# Main_PCB.net
KiCad netlist of a schematic drawn in Altium Designer
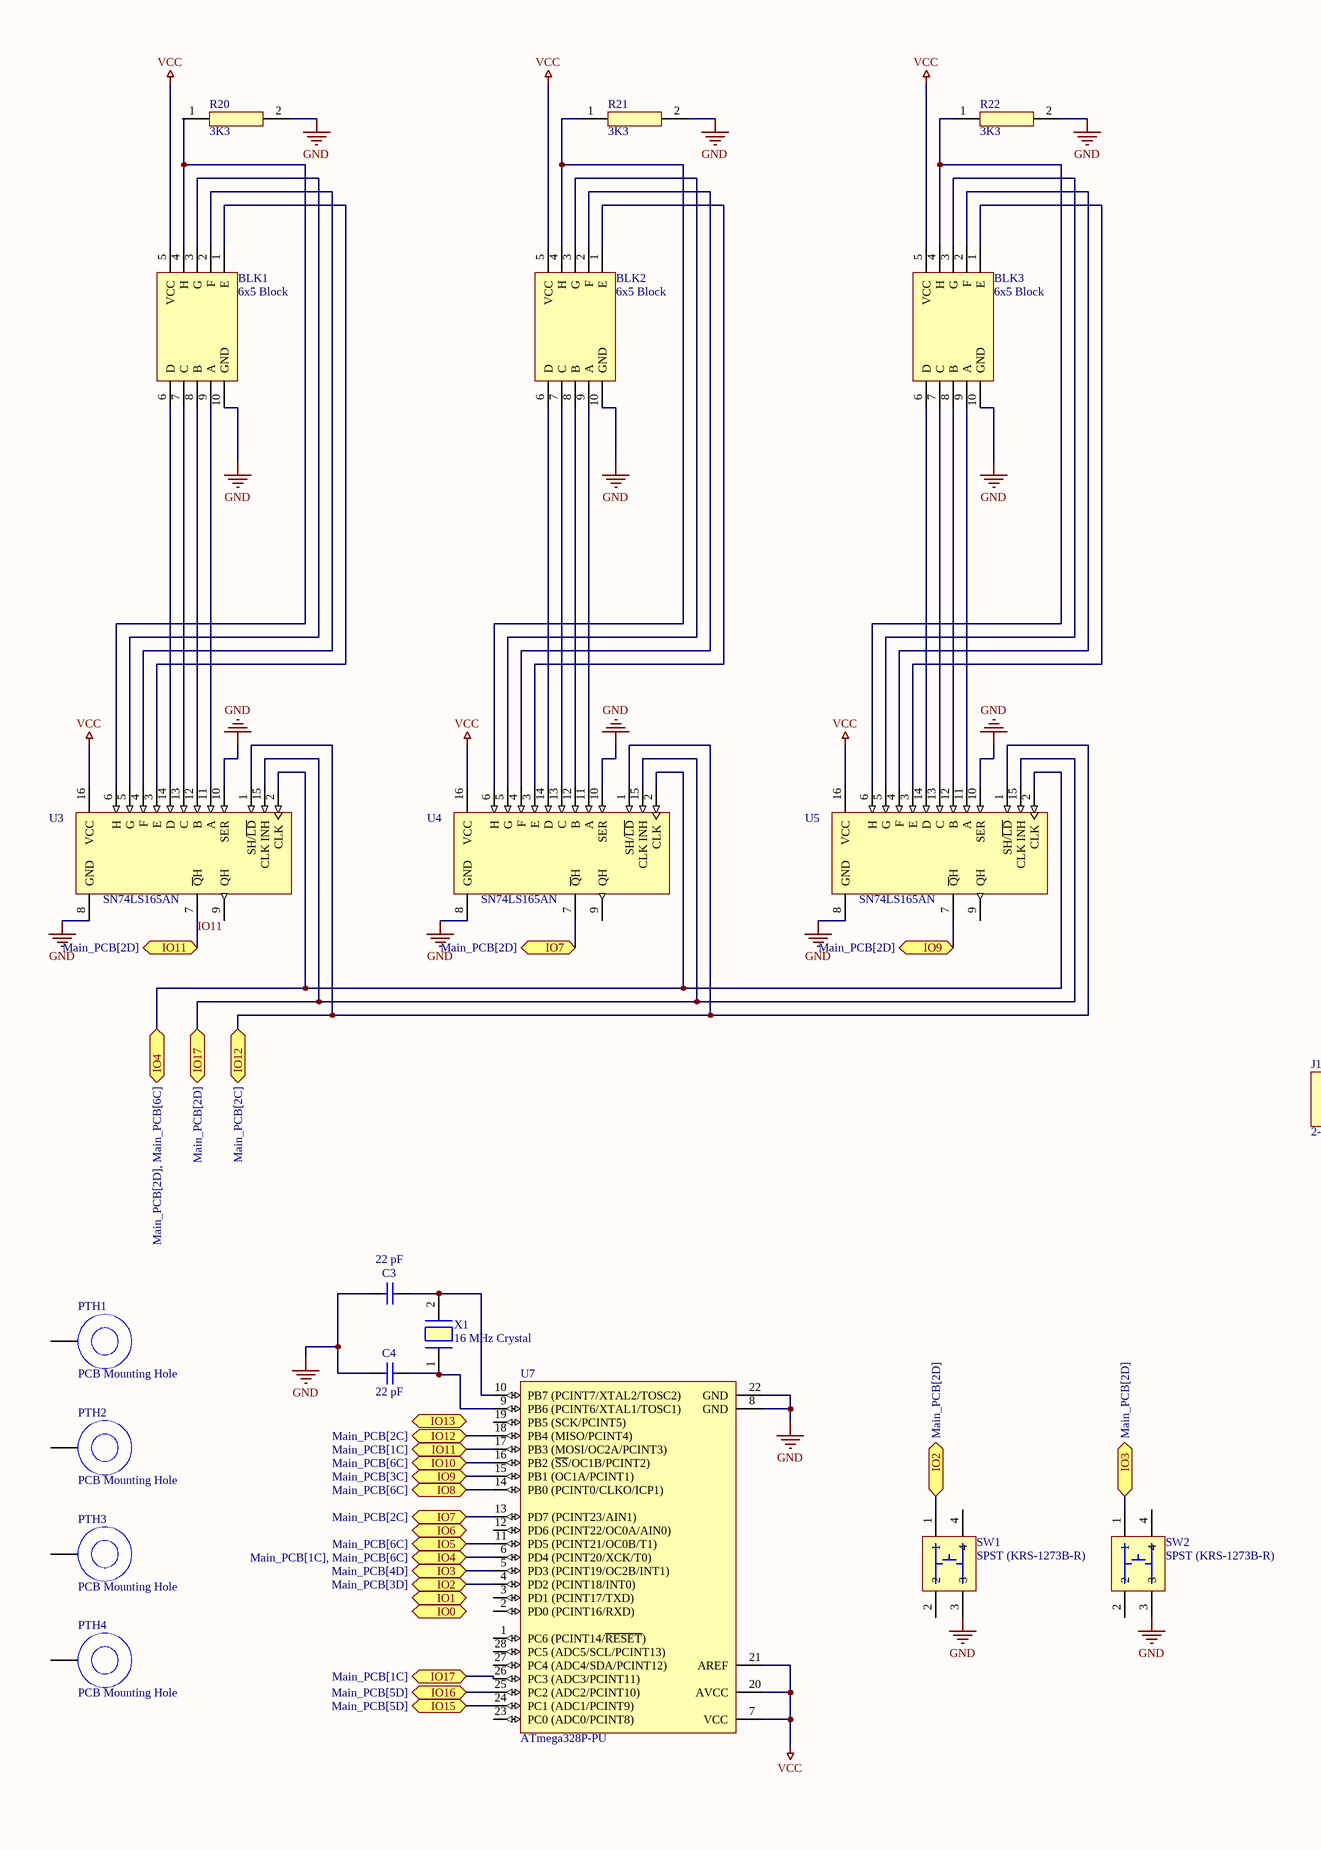
[diagram p0: Main_PCB.SchDoc, left]
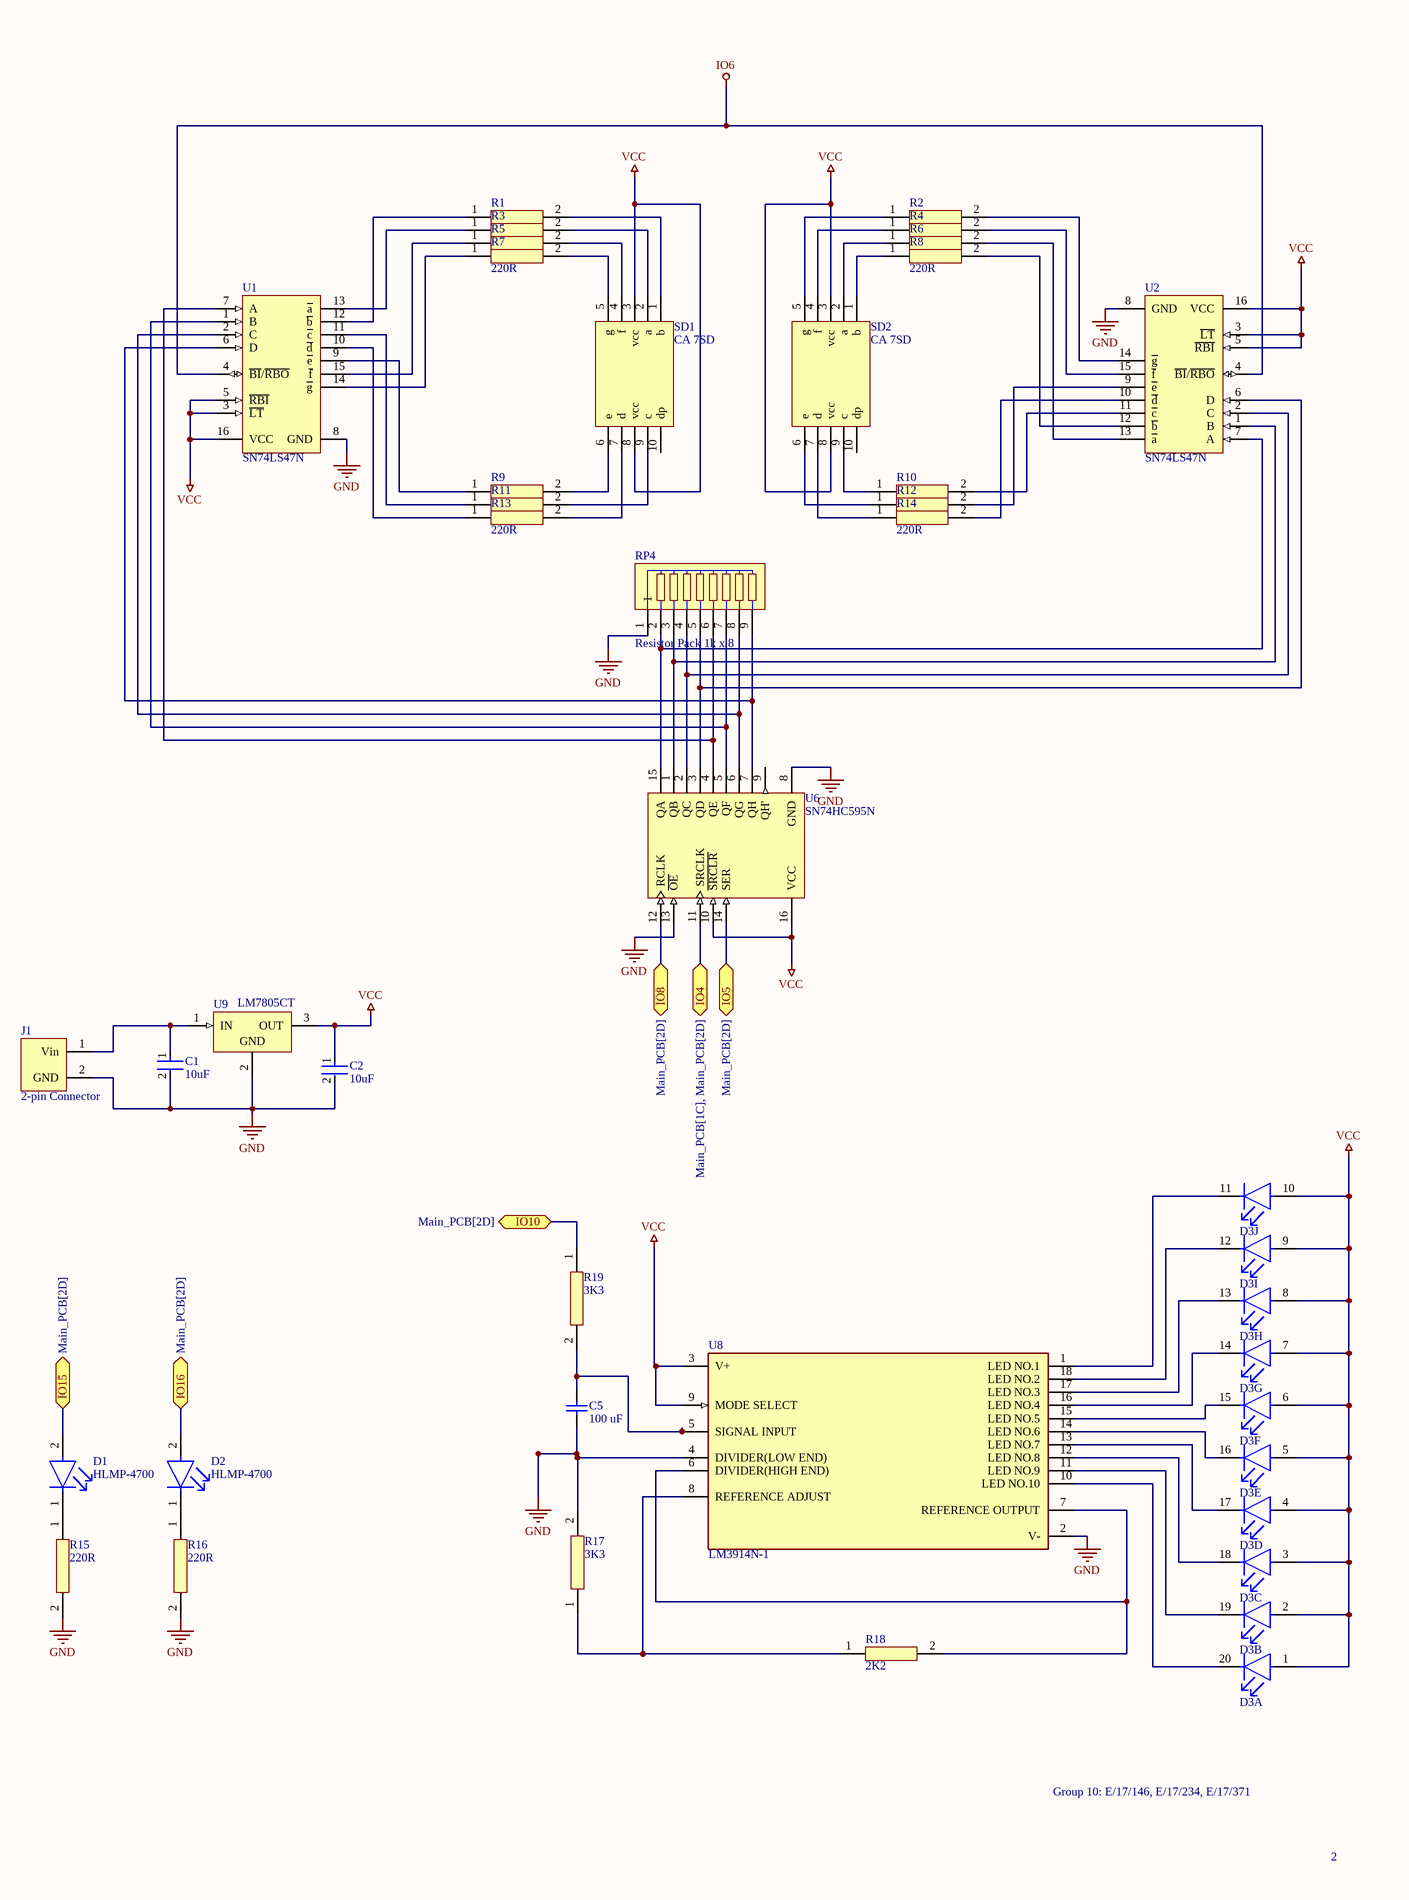
[diagram p1: Main_PCB.SchDoc, right]

(export (version "E")
  (design (tool "Eeschema 10.0.6"))
  (components
    (comp (ref "BLK1")
      (value "6x5 Block")
      (footprint "Block_6x5")
      (libsource (lib "Schlib1") (part "Block_6x5"))
    )
    (comp (ref "BLK2")
      (value "6x5 Block")
      (footprint "Block_6x5")
      (libsource (lib "Schlib1") (part "Block_6x5"))
    )
    (comp (ref "BLK3")
      (value "6x5 Block")
      (footprint "Block_6x5")
      (libsource (lib "Schlib1") (part "Block_6x5"))
    )
    (comp (ref "C1")
      (value "10uF")
      (footprint "FP-RCE3DB-MFG")
      (description "Cap Ceramic 10uF 25V X7R ±10% Radial 2.5mm +125°C Automotive Bulk (RCER71E106K3A2H03B)")
      (fields (field (name "TOLERANCE") "10%"))
      (libsource (lib "Altium Content Vault") (part "b4654b650e69147ec39a6b967a45e02"))
    )
    (comp (ref "C2")
      (value "10uF")
      (footprint "FP-RCE3DB-MFG")
      (description "Cap Ceramic 10uF 25V X7R ±10% Radial 2.5mm +125°C Automotive Bulk (RCER71E106K3A2H03B)")
      (fields (field (name "TOLERANCE") "10%"))
      (libsource (lib "Altium Content Vault") (part "b4654b650e69147ec39a6b967a45e02"))
    )
    (comp (ref "C3")
      (value "22 pF")
      (footprint "KEMT-C315-THT-2")
      (description "Capacitor, Ceramic, 22 pF, +/-10 %, 100 V, -55 to 125 degC, 2-Pin THD, RoHS, Bulk")
      (libsource (lib "Altium Content Vault") (part "CAP-NP-2"))
    )
    (comp (ref "C4")
      (value "22 pF")
      (footprint "KEMT-C315-THT-2")
      (description "Capacitor, Ceramic, 22 pF, +/-10 %, 100 V, -55 to 125 degC, 2-Pin THD, RoHS, Bulk")
      (libsource (lib "Altium Content Vault") (part "CAP-NP-2"))
    )
    (comp (ref "C5")
      (value "100 uF")
      (footprint "KEMT-C315-THT-2")
      (description "Capacitor, Ceramic, 100 uF, +/-10 %, 100 V, -55 to 125 degC, 2-Pin THD, RoHS, Bulk")
      (libsource (lib "Altium Content Vault") (part "CAP-NP-2"))
    )
    (comp (ref "D1")
      (value "HLMP-4700")
      (footprint "FP-HLMP-4700-MFG")
      (description "LED RED DIFFUSED T-1 3/4 T/H")
      (fields
        (field (name "OCTOPART") "https://octopart.com/hlmp-4700-broadcom-71130526")
        (field (name "MANUFACTURER") "Broadcom")
      )
      (libsource (lib "Altium Content Vault") (part "8706943c75ba83719d021d2fdc84c58"))
    )
    (comp (ref "D2")
      (value "HLMP-4700")
      (footprint "FP-HLMP-4700-MFG")
      (description "LED RED DIFFUSED T-1 3/4 T/H")
      (fields
        (field (name "OCTOPART") "https://octopart.com/hlmp-4700-broadcom-71130526")
        (field (name "MANUFACTURER") "Broadcom")
      )
      (libsource (lib "Altium Content Vault") (part "8706943c75ba83719d021d2fdc84c58"))
    )
    (comp (ref "D3")
      (value "SSA-LXB10HW-GF/LP")
      (footprint "FP-SSA-LXB10HW-GF-LP-MFG")
      (description "LED ARRAY 10X25MM 10SEG RED DIFF")
      (fields
        (field (name "OCTOPART") "https://octopart.com/ssa-lxb10hw-gf%2Flp-lumex-548235")
        (field (name "MANUFACTURER") "lumex")
      )
      (libsource (lib "Altium Content Vault") (part "0ad3f8813297581e4dba16f0763b6c7"))
    )
    (comp (ref "J1")
      (value "2-pin Connector")
      (footprint "2-pin Connector")
      (description "Female, 2C, Straight, .100\"CC; 3.20mm Tail, No Mt. 100u\" Tin; PBT, Phos Bronze, 105 C")
      (fields
        (field (name "MANUFACTURER") "Sullins")
        (field (name "MANUFACTURER PART NUMBER") "PPTC021LFBN-RC")
      )
      (libsource (lib "Schlib1") (part "PPTC021LFBN-RC"))
    )
    (comp (ref "PTH1")
      (value "PCB Mounting Hole")
      (footprint "PTH 2mm")
      (libsource (lib "Schlib1") (part "PTH"))
    )
    (comp (ref "PTH2")
      (value "PCB Mounting Hole")
      (footprint "PTH 2mm")
      (libsource (lib "Schlib1") (part "PTH"))
    )
    (comp (ref "PTH3")
      (value "PCB Mounting Hole")
      (footprint "PTH 2mm")
      (libsource (lib "Schlib1") (part "PTH"))
    )
    (comp (ref "PTH4")
      (value "PCB Mounting Hole")
      (footprint "PTH 2mm")
      (libsource (lib "Schlib1") (part "PTH"))
    )
    (comp (ref "R1")
      (value "220R")
      (footprint "CFR_400mil")
      (description "General Type Carbon Film Resistor 220Ohm 1/4W 5% Axial Bulk")
      (fields
        (field (name "MANUFACTURER") "Yageo")
        (field (name "MANUFACTURER PART NUMBER") "CFR-25JB-52-220R")
      )
      (libsource (lib "Schlib1") (part "CFR-25JB-52-220R"))
    )
    (comp (ref "R2")
      (value "220R")
      (footprint "CFR_400mil")
      (description "General Type Carbon Film Resistor 220Ohm 1/4W 5% Axial Bulk")
      (fields
        (field (name "MANUFACTURER") "Yageo")
        (field (name "MANUFACTURER PART NUMBER") "CFR-25JB-52-220R")
      )
      (libsource (lib "Schlib1") (part "CFR-25JB-52-220R"))
    )
    (comp (ref "R3")
      (value "220R")
      (footprint "CFR_400mil")
      (description "General Type Carbon Film Resistor 220Ohm 1/4W 5% Axial Bulk")
      (fields
        (field (name "MANUFACTURER") "Yageo")
        (field (name "MANUFACTURER PART NUMBER") "CFR-25JB-52-220R")
      )
      (libsource (lib "Schlib1") (part "CFR-25JB-52-220R"))
    )
    (comp (ref "R4")
      (value "220R")
      (footprint "CFR_400mil")
      (description "General Type Carbon Film Resistor 220Ohm 1/4W 5% Axial Bulk")
      (fields
        (field (name "MANUFACTURER") "Yageo")
        (field (name "MANUFACTURER PART NUMBER") "CFR-25JB-52-220R")
      )
      (libsource (lib "Schlib1") (part "CFR-25JB-52-220R"))
    )
    (comp (ref "R5")
      (value "220R")
      (footprint "CFR_400mil")
      (description "General Type Carbon Film Resistor 220Ohm 1/4W 5% Axial Bulk")
      (fields
        (field (name "MANUFACTURER") "Yageo")
        (field (name "MANUFACTURER PART NUMBER") "CFR-25JB-52-220R")
      )
      (libsource (lib "Schlib1") (part "CFR-25JB-52-220R"))
    )
    (comp (ref "R6")
      (value "220R")
      (footprint "CFR_400mil")
      (description "General Type Carbon Film Resistor 220Ohm 1/4W 5% Axial Bulk")
      (fields
        (field (name "MANUFACTURER") "Yageo")
        (field (name "MANUFACTURER PART NUMBER") "CFR-25JB-52-220R")
      )
      (libsource (lib "Schlib1") (part "CFR-25JB-52-220R"))
    )
    (comp (ref "R7")
      (value "220R")
      (footprint "CFR_400mil")
      (description "General Type Carbon Film Resistor 220Ohm 1/4W 5% Axial Bulk")
      (fields
        (field (name "MANUFACTURER") "Yageo")
        (field (name "MANUFACTURER PART NUMBER") "CFR-25JB-52-220R")
      )
      (libsource (lib "Schlib1") (part "CFR-25JB-52-220R"))
    )
    (comp (ref "R8")
      (value "220R")
      (footprint "CFR_400mil")
      (description "General Type Carbon Film Resistor 220Ohm 1/4W 5% Axial Bulk")
      (fields
        (field (name "MANUFACTURER") "Yageo")
        (field (name "MANUFACTURER PART NUMBER") "CFR-25JB-52-220R")
      )
      (libsource (lib "Schlib1") (part "CFR-25JB-52-220R"))
    )
    (comp (ref "R9")
      (value "220R")
      (footprint "CFR_400mil")
      (description "General Type Carbon Film Resistor 220Ohm 1/4W 5% Axial Bulk")
      (fields
        (field (name "MANUFACTURER") "Yageo")
        (field (name "MANUFACTURER PART NUMBER") "CFR-25JB-52-220R")
      )
      (libsource (lib "Schlib1") (part "CFR-25JB-52-220R"))
    )
    (comp (ref "R10")
      (value "220R")
      (footprint "CFR_400mil")
      (description "General Type Carbon Film Resistor 220Ohm 1/4W 5% Axial Bulk")
      (fields
        (field (name "MANUFACTURER") "Yageo")
        (field (name "MANUFACTURER PART NUMBER") "CFR-25JB-52-220R")
      )
      (libsource (lib "Schlib1") (part "CFR-25JB-52-220R"))
    )
    (comp (ref "R11")
      (value "220R")
      (footprint "CFR_400mil")
      (description "General Type Carbon Film Resistor 220Ohm 1/4W 5% Axial Bulk")
      (fields
        (field (name "MANUFACTURER") "Yageo")
        (field (name "MANUFACTURER PART NUMBER") "CFR-25JB-52-220R")
      )
      (libsource (lib "Schlib1") (part "CFR-25JB-52-220R"))
    )
    (comp (ref "R12")
      (value "220R")
      (footprint "CFR_400mil")
      (description "General Type Carbon Film Resistor 220Ohm 1/4W 5% Axial Bulk")
      (fields
        (field (name "MANUFACTURER") "Yageo")
        (field (name "MANUFACTURER PART NUMBER") "CFR-25JB-52-220R")
      )
      (libsource (lib "Schlib1") (part "CFR-25JB-52-220R"))
    )
    (comp (ref "R13")
      (value "220R")
      (footprint "CFR_400mil")
      (description "General Type Carbon Film Resistor 220Ohm 1/4W 5% Axial Bulk")
      (fields
        (field (name "MANUFACTURER") "Yageo")
        (field (name "MANUFACTURER PART NUMBER") "CFR-25JB-52-220R")
      )
      (libsource (lib "Schlib1") (part "CFR-25JB-52-220R"))
    )
    (comp (ref "R14")
      (value "220R")
      (footprint "CFR_400mil")
      (description "General Type Carbon Film Resistor 220Ohm 1/4W 5% Axial Bulk")
      (fields
        (field (name "MANUFACTURER") "Yageo")
        (field (name "MANUFACTURER PART NUMBER") "CFR-25JB-52-220R")
      )
      (libsource (lib "Schlib1") (part "CFR-25JB-52-220R"))
    )
    (comp (ref "R15")
      (value "220R")
      (footprint "CFR_400mil")
      (description "General Type Carbon Film Resistor 220Ohm 1/4W 5% Axial Bulk")
      (fields
        (field (name "MANUFACTURER") "Yageo")
        (field (name "MANUFACTURER PART NUMBER") "CFR-25JB-52-220R")
      )
      (libsource (lib "") (part "CFR-25JB-52-220R_1"))
    )
    (comp (ref "R16")
      (value "220R")
      (footprint "CFR_400mil")
      (description "General Type Carbon Film Resistor 220Ohm 1/4W 5% Axial Bulk")
      (fields
        (field (name "MANUFACTURER") "Yageo")
        (field (name "MANUFACTURER PART NUMBER") "CFR-25JB-52-220R")
      )
      (libsource (lib "") (part "CFR-25JB-52-220R_1"))
    )
    (comp (ref "R17")
      (value "3K3")
      (footprint "CFR_400mil")
      (description "General Type Carbon Film Resistor 3.3kOhm 1/4W 5% Axial Bulk")
      (fields
        (field (name "MANUFACTURER") "Yageo")
        (field (name "MANUFACTURER PART NUMBER") "CFR-25JB-52-220R")
      )
      (libsource (lib "") (part "CFR-25JB-52-3K3_2"))
    )
    (comp (ref "R18")
      (value "2K2")
      (footprint "CFR_400mil")
      (description "General Type Carbon Film Resistor 2.2kOhm 1/4W 5% Axial Bulk")
      (fields
        (field (name "MANUFACTURER") "Yageo")
        (field (name "MANUFACTURER PART NUMBER") "CFR-25JB-52-220R")
      )
      (libsource (lib "Schlib1") (part "CFR-25JB-52-2K2"))
    )
    (comp (ref "R19")
      (value "3K3")
      (footprint "CFR_400mil")
      (description "General Type Carbon Film Resistor 3.3kOhm 1/4W 5% Axial Bulk")
      (fields
        (field (name "MANUFACTURER") "Yageo")
        (field (name "MANUFACTURER PART NUMBER") "CFR-25JB-52-220R")
      )
      (libsource (lib "") (part "CFR-25JB-52-3K3_1"))
    )
    (comp (ref "R20")
      (value "3K3")
      (footprint "CFR_400mil")
      (description "General Type Carbon Film Resistor 3.3kOhm 1/4W 5% Axial Bulk")
      (fields
        (field (name "MANUFACTURER") "Yageo")
        (field (name "MANUFACTURER PART NUMBER") "CFR-25JB-52-220R")
      )
      (libsource (lib "Schlib1") (part "CFR-25JB-52-3K3"))
    )
    (comp (ref "R21")
      (value "3K3")
      (footprint "CFR_400mil")
      (description "General Type Carbon Film Resistor 3.3kOhm 1/4W 5% Axial Bulk")
      (fields
        (field (name "MANUFACTURER") "Yageo")
        (field (name "MANUFACTURER PART NUMBER") "CFR-25JB-52-220R")
      )
      (libsource (lib "Schlib1") (part "CFR-25JB-52-3K3"))
    )
    (comp (ref "R22")
      (value "3K3")
      (footprint "CFR_400mil")
      (description "General Type Carbon Film Resistor 3.3kOhm 1/4W 5% Axial Bulk")
      (fields
        (field (name "MANUFACTURER") "Yageo")
        (field (name "MANUFACTURER PART NUMBER") "CFR-25JB-52-220R")
      )
      (libsource (lib "Schlib1") (part "CFR-25JB-52-3K3"))
    )
    (comp (ref "RP4")
      (value "Resistor Pack 1k x 8")
      (footprint "Resistor Pack 1k x 8")
      (description "Res Thick Film NET 1K Ohm 2% 1.13W ±100ppm/°C BUS Molded 9-Pin SIP Pin Thru-Hole")
      (fields
        (field (name "MANUFACTURER") "Bourns")
        (field (name "MANUFACTURER PART NUMBER") "4309R-101-102LF")
      )
      (libsource (lib "Schlib1") (part "4309R-101-102LF"))
    )
    (comp (ref "SD1")
      (value "CA 7SD")
      (footprint "CA 7SD")
      (description "Single Digit Seven Segment Green 0.56\" Common Anode Through Hole LED Display")
      (fields (field (name "MANUFACTURER") "Lumex") (field (name "MANUFACTURER PART NUMBER") "LDS-A5642RI"))
      (libsource (lib "Schlib1") (part "LDS-A5642RI"))
    )
    (comp (ref "SD2")
      (value "CA 7SD")
      (footprint "CA 7SD")
      (description "Single Digit Seven Segment Green 0.56\" Common Anode Through Hole LED Display")
      (fields (field (name "MANUFACTURER") "Lumex") (field (name "MANUFACTURER PART NUMBER") "LDS-A5642RI"))
      (libsource (lib "Schlib1") (part "LDS-A5642RI"))
    )
    (comp (ref "SW1")
      (value "SPST (KRS-1273B-R)")
      (footprint "SPST KRS-1273B-R")
      (description "Switch Push Button Tactile Off Momentary (On) Single Pole Single Throw Cap: 155389 155409")
      (fields
        (field (name "MANUFACTURER") "Jameco Valuepro")
        (field (name "MANUFACTURER PART NUMBER") "KRS-1273B-R")
      )
      (libsource (lib "Schlib1") (part "KRS-1273B-R"))
    )
    (comp (ref "SW2")
      (value "SPST (KRS-1273B-R)")
      (footprint "SPST KRS-1273B-R")
      (description "Switch Push Button Tactile Off Momentary (On) Single Pole Single Throw Cap: 155389 155409")
      (fields
        (field (name "MANUFACTURER") "Jameco Valuepro")
        (field (name "MANUFACTURER PART NUMBER") "KRS-1273B-R")
      )
      (libsource (lib "Schlib1") (part "KRS-1273B-R"))
    )
    (comp (ref "U1")
      (value "SN74LS47N")
      (footprint "N0016A")
      (description "BCD-to-7-Segment Decoder / Driver, 4.75 to 5.25 V, 0 to 70 degC, 16-pin DIP (N16), Pb-Free (RoHS)")
      (fields (field (name "MANUFACTURER") "Texas Instruments"))
      (libsource (lib "Altium Content Vault") (part "TI-SNX4XX247-16"))
    )
    (comp (ref "U2")
      (value "SN74LS47N")
      (footprint "N0016A")
      (description "BCD-to-7-Segment Decoder / Driver, 4.75 to 5.25 V, 0 to 70 degC, 16-pin DIP (N16), Pb-Free (RoHS)")
      (fields (field (name "MANUFACTURER") "Texas Instruments"))
      (libsource (lib "") (part "TI-SNX4XX247-16_1"))
    )
    (comp (ref "U3")
      (value "SN74LS165AN")
      (footprint "N0016A")
      (description "Serial-out shift registers, N0016A, TUBE")
      (fields
        (field (name "GENERIC PART NUMBER") "SN74LS165A")
        (field (name "MANUFACTURER") "Texas Instruments")
      )
      (libsource (lib "Altium Content Vault") (part "TI-SNX4XXX165X-16"))
    )
    (comp (ref "U4")
      (value "SN74LS165AN")
      (footprint "N0016A")
      (description "Serial-out shift registers, N0016A, TUBE")
      (fields
        (field (name "GENERIC PART NUMBER") "SN74LS165A")
        (field (name "MANUFACTURER") "Texas Instruments")
      )
      (libsource (lib "Altium Content Vault") (part "TI-SNX4XXX165X-16"))
    )
    (comp (ref "U5")
      (value "SN74LS165AN")
      (footprint "N0016A")
      (description "Serial-out shift registers, N0016A, TUBE")
      (fields
        (field (name "GENERIC PART NUMBER") "SN74LS165A")
        (field (name "MANUFACTURER") "Texas Instruments")
      )
      (libsource (lib "Altium Content Vault") (part "TI-SNX4XXX165X-16"))
    )
    (comp (ref "U6")
      (value "SN74HC595N")
      (footprint "N0016A")
      (description "8-Bit Shift Registers With 3-State Output Registers, N0016A, TUBE")
      (fields
        (field (name "GENERIC PART NUMBER") "SN74HC595")
        (field (name "MANUFACTURER") "Texas Instruments")
      )
      (libsource (lib "Altium Content Vault") (part "TI-SN74XHCT595X_SN74LV595A-16"))
    )
    (comp (ref "U7")
      (value "ATmega328P-PU")
      (footprint "28P3")
      (libsource (lib "Altium Content Vault") (part "MC-8B-ATM48-IL28"))
    )
    (comp (ref "U8")
      (value "LM3914N-1")
      (footprint "FP-NFK0018A-MFG")
      (description "IC DRVR DOT/BAR DISPLAY 18DIP")
      (libsource (lib "Altium Content Vault") (part "8d9105b9cf50def005be23956edfdd2"))
    )
    (comp (ref "U9")
      (value "LM7805CT")
      (footprint "FAIR-TO-220-3")
      (description "Positive Voltage Regulator, 5 V, 1 A, -40 to 125 degC, 3-Pin TO-220, RoHS, Tube")
      (fields (field (name "MANUFACTURER") "FairchildSemiconductor"))
      (libsource (lib "Altium Content Vault") (part "FAIR-LM7805CT-TO220-3"))
    )
    (comp (ref "X1")
      (value "16 MHz Crystal")
      (footprint "Crystal Osc TH")
      (description "Crystal 16MHz ±50ppm (Tol) ±50ppm (Stability) 20pF FUND 30Ohm 2-Pin DIP HC-49/S Thru-Hole Bulk")
      (fields (field (name "MANUFACTURER") "TXC") (field (name "MANUFACTURER PART NUMBER") "9B-16.000MBBK-B"))
      (libsource (lib "Schlib1") (part "9B-16.000MBBK-B"))
    )
  )
  (nets
    (net (code "3") (name "/IO2") (class "Default")
      (node (ref "SW1") (pin "1") (pinfunction "1_1") (pintype "passive"))
      (node (ref "U7") (pin "4") (pinfunction "PD2_(PCINT18/INT0)_4") (pintype "bidirectional"))
    )
    (net (code "4") (name "/IO3") (class "Default")
      (node (ref "SW2") (pin "1") (pinfunction "1_1") (pintype "passive"))
      (node (ref "U7") (pin "5") (pinfunction "PD3_(PCINT19/OC2B/INT1)_5") (pintype "bidirectional"))
    )
    (net (code "5") (name "/IO4") (class "Default")
      (node (ref "U3") (pin "2") (pinfunction "CLK_2") (pintype "input"))
      (node (ref "U4") (pin "2") (pinfunction "CLK_2") (pintype "input"))
      (node (ref "U5") (pin "2") (pinfunction "CLK_2") (pintype "input"))
      (node (ref "U6") (pin "11") (pinfunction "SRCLK_11") (pintype "input"))
      (node (ref "U7") (pin "6") (pinfunction "PD4_(PCINT20/XCK/T0)_6") (pintype "bidirectional"))
    )
    (net (code "6") (name "/IO5") (class "Default")
      (node (ref "U6") (pin "14") (pinfunction "SER_14") (pintype "input"))
      (node (ref "U7") (pin "11") (pinfunction "PD5_(PCINT21/OC0B/T1)_11") (pintype "bidirectional"))
    )
    (net (code "7") (name "/IO7") (class "Default")
      (node (ref "U4") (pin "7") (pinfunction "~{Q}H_7") (pintype "passive"))
      (node (ref "U7") (pin "13") (pinfunction "PD7_(PCINT23/AIN1)_13") (pintype "bidirectional"))
    )
    (net (code "8") (name "/IO8") (class "Default")
      (node (ref "U6") (pin "12") (pinfunction "RCLK_12") (pintype "input"))
      (node (ref "U7") (pin "14") (pinfunction "PB0_(PCINT0/CLKO/ICP1)_14") (pintype "bidirectional"))
    )
    (net (code "9") (name "/IO9") (class "Default")
      (node (ref "U5") (pin "7") (pinfunction "~{Q}H_7") (pintype "passive"))
      (node (ref "U7") (pin "15") (pinfunction "PB1_(OC1A/PCINT1)_15") (pintype "bidirectional"))
    )
    (net (code "10") (name "/IO10") (class "Default")
      (node (ref "R19") (pin "1") (pinfunction "1_1") (pintype "passive"))
      (node (ref "U7") (pin "16") (pinfunction "PB2_(~{SS}/OC1B/PCINT2)_16") (pintype "bidirectional"))
    )
    (net (code "11") (name "/IO11") (class "Default")
      (node (ref "U3") (pin "7") (pinfunction "~{Q}H_7") (pintype "passive"))
      (node (ref "U7") (pin "17") (pinfunction "PB3_(MOSI/OC2A/PCINT3)_17") (pintype "bidirectional"))
    )
    (net (code "12") (name "/IO12") (class "Default")
      (node (ref "U3") (pin "1") (pinfunction "SH/~{LD}_1") (pintype "input"))
      (node (ref "U4") (pin "1") (pinfunction "SH/~{LD}_1") (pintype "input"))
      (node (ref "U5") (pin "1") (pinfunction "SH/~{LD}_1") (pintype "input"))
      (node (ref "U7") (pin "18") (pinfunction "PB4_(MISO/PCINT4)_18") (pintype "bidirectional"))
    )
    (net (code "14") (name "/IO15") (class "Default")
      (node (ref "D1") (pin "2") (pinfunction "A_2") (pintype "passive"))
      (node (ref "U7") (pin "24") (pinfunction "PC1_(ADC1/PCINT9)_24") (pintype "bidirectional"))
    )
    (net (code "15") (name "/IO16") (class "Default")
      (node (ref "D2") (pin "2") (pinfunction "A_2") (pintype "passive"))
      (node (ref "U7") (pin "25") (pinfunction "PC2_(ADC2/PCINT10)_25") (pintype "bidirectional"))
    )
    (net (code "16") (name "/IO17") (class "Default")
      (node (ref "U3") (pin "15") (pinfunction "CLK_INH_15") (pintype "input"))
      (node (ref "U4") (pin "15") (pinfunction "CLK_INH_15") (pintype "input"))
      (node (ref "U5") (pin "15") (pinfunction "CLK_INH_15") (pintype "input"))
      (node (ref "U7") (pin "26") (pinfunction "PC3_(ADC3/PCINT11)_26") (pintype "bidirectional"))
    )
    (net (code "17") (name "GND") (class "Default")
      (node (ref "BLK1") (pin "10") (pinfunction "GND_10") (pintype "passive"))
      (node (ref "BLK2") (pin "10") (pinfunction "GND_10") (pintype "passive"))
      (node (ref "BLK3") (pin "10") (pinfunction "GND_10") (pintype "passive"))
      (node (ref "C1") (pin "2") (pinfunction "2_2") (pintype "passive"))
      (node (ref "C2") (pin "2") (pinfunction "2_2") (pintype "passive"))
      (node (ref "C3") (pin "1") (pinfunction "1_1") (pintype "passive"))
      (node (ref "C4") (pin "1") (pinfunction "1_1") (pintype "passive"))
      (node (ref "C5") (pin "1") (pinfunction "1_1") (pintype "passive"))
      (node (ref "J1") (pin "2") (pinfunction "GND_2") (pintype "passive"))
      (node (ref "R15") (pin "2") (pinfunction "2_2") (pintype "passive"))
      (node (ref "R16") (pin "2") (pinfunction "2_2") (pintype "passive"))
      (node (ref "R17") (pin "2") (pinfunction "2_2") (pintype "passive"))
      (node (ref "R20") (pin "2") (pinfunction "2_2") (pintype "passive"))
      (node (ref "R21") (pin "2") (pinfunction "2_2") (pintype "passive"))
      (node (ref "R22") (pin "2") (pinfunction "2_2") (pintype "passive"))
      (node (ref "RP4") (pin "1") (pinfunction "1_1") (pintype "passive"))
      (node (ref "SW1") (pin "3") (pinfunction "3_3") (pintype "passive"))
      (node (ref "SW2") (pin "3") (pinfunction "3_3") (pintype "passive"))
      (node (ref "U1") (pin "8") (pinfunction "GND_8") (pintype "power_in"))
      (node (ref "U2") (pin "8") (pinfunction "GND_8") (pintype "power_in"))
      (node (ref "U3") (pin "10") (pinfunction "SER_10") (pintype "input"))
      (node (ref "U3") (pin "8") (pinfunction "GND_8") (pintype "power_in"))
      (node (ref "U4") (pin "10") (pinfunction "SER_10") (pintype "input"))
      (node (ref "U4") (pin "8") (pinfunction "GND_8") (pintype "power_in"))
      (node (ref "U5") (pin "10") (pinfunction "SER_10") (pintype "input"))
      (node (ref "U5") (pin "8") (pinfunction "GND_8") (pintype "power_in"))
      (node (ref "U6") (pin "13") (pinfunction "~{OE}_13") (pintype "input"))
      (node (ref "U6") (pin "8") (pinfunction "GND_8") (pintype "power_in"))
      (node (ref "U7") (pin "22") (pinfunction "GND_22") (pintype "power_in"))
      (node (ref "U7") (pin "8") (pinfunction "GND_8") (pintype "power_in"))
      (node (ref "U8") (pin "2") (pinfunction "V-_2") (pintype "power_in"))
      (node (ref "U8") (pin "4") (pinfunction "DIVIDER(LOW_END)_4") (pintype "passive"))
      (node (ref "U9") (pin "2") (pinfunction "GND_2") (pintype "power_in"))
    )
    (net (code "18") (name "IO6") (class "Default")
      (node (ref "U1") (pin "4") (pinfunction "~{BI}/~{RBO}_4") (pintype "bidirectional"))
      (node (ref "U2") (pin "4") (pinfunction "~{BI}/~{RBO}_4") (pintype "bidirectional"))
    )
    (net (code "19") (name "Net-(BLK1-A)") (class "Default")
      (node (ref "BLK1") (pin "9") (pinfunction "A_9") (pintype "passive"))
      (node (ref "U3") (pin "11") (pinfunction "A_11") (pintype "input"))
    )
    (net (code "20") (name "Net-(BLK1-B)") (class "Default")
      (node (ref "BLK1") (pin "8") (pinfunction "B_8") (pintype "passive"))
      (node (ref "U3") (pin "12") (pinfunction "B_12") (pintype "input"))
    )
    (net (code "21") (name "Net-(BLK1-C)") (class "Default")
      (node (ref "BLK1") (pin "7") (pinfunction "C_7") (pintype "passive"))
      (node (ref "U3") (pin "13") (pinfunction "C_13") (pintype "input"))
    )
    (net (code "22") (name "Net-(BLK1-D)") (class "Default")
      (node (ref "BLK1") (pin "6") (pinfunction "D_6") (pintype "passive"))
      (node (ref "U3") (pin "14") (pinfunction "D_14") (pintype "input"))
    )
    (net (code "23") (name "Net-(BLK1-E)") (class "Default")
      (node (ref "BLK1") (pin "1") (pinfunction "E_1") (pintype "passive"))
      (node (ref "U3") (pin "3") (pinfunction "E_3") (pintype "input"))
    )
    (net (code "24") (name "Net-(BLK1-F)") (class "Default")
      (node (ref "BLK1") (pin "2") (pinfunction "F_2") (pintype "passive"))
      (node (ref "U3") (pin "4") (pinfunction "F_4") (pintype "input"))
    )
    (net (code "25") (name "Net-(BLK1-G)") (class "Default")
      (node (ref "BLK1") (pin "3") (pinfunction "G_3") (pintype "passive"))
      (node (ref "U3") (pin "5") (pinfunction "G_5") (pintype "input"))
    )
    (net (code "26") (name "Net-(BLK1-H)") (class "Default")
      (node (ref "BLK1") (pin "4") (pinfunction "H_4") (pintype "passive"))
      (node (ref "R20") (pin "1") (pinfunction "1_1") (pintype "passive"))
      (node (ref "U3") (pin "6") (pinfunction "H_6") (pintype "input"))
    )
    (net (code "27") (name "Net-(BLK2-A)") (class "Default")
      (node (ref "BLK2") (pin "9") (pinfunction "A_9") (pintype "passive"))
      (node (ref "U4") (pin "11") (pinfunction "A_11") (pintype "input"))
    )
    (net (code "28") (name "Net-(BLK2-B)") (class "Default")
      (node (ref "BLK2") (pin "8") (pinfunction "B_8") (pintype "passive"))
      (node (ref "U4") (pin "12") (pinfunction "B_12") (pintype "input"))
    )
    (net (code "29") (name "Net-(BLK2-C)") (class "Default")
      (node (ref "BLK2") (pin "7") (pinfunction "C_7") (pintype "passive"))
      (node (ref "U4") (pin "13") (pinfunction "C_13") (pintype "input"))
    )
    (net (code "30") (name "Net-(BLK2-D)") (class "Default")
      (node (ref "BLK2") (pin "6") (pinfunction "D_6") (pintype "passive"))
      (node (ref "U4") (pin "14") (pinfunction "D_14") (pintype "input"))
    )
    (net (code "31") (name "Net-(BLK2-E)") (class "Default")
      (node (ref "BLK2") (pin "1") (pinfunction "E_1") (pintype "passive"))
      (node (ref "U4") (pin "3") (pinfunction "E_3") (pintype "input"))
    )
    (net (code "32") (name "Net-(BLK2-F)") (class "Default")
      (node (ref "BLK2") (pin "2") (pinfunction "F_2") (pintype "passive"))
      (node (ref "U4") (pin "4") (pinfunction "F_4") (pintype "input"))
    )
    (net (code "33") (name "Net-(BLK2-G)") (class "Default")
      (node (ref "BLK2") (pin "3") (pinfunction "G_3") (pintype "passive"))
      (node (ref "U4") (pin "5") (pinfunction "G_5") (pintype "input"))
    )
    (net (code "34") (name "Net-(BLK2-H)") (class "Default")
      (node (ref "BLK2") (pin "4") (pinfunction "H_4") (pintype "passive"))
      (node (ref "R21") (pin "1") (pinfunction "1_1") (pintype "passive"))
      (node (ref "U4") (pin "6") (pinfunction "H_6") (pintype "input"))
    )
    (net (code "35") (name "Net-(BLK3-A)") (class "Default")
      (node (ref "BLK3") (pin "9") (pinfunction "A_9") (pintype "passive"))
      (node (ref "U5") (pin "11") (pinfunction "A_11") (pintype "input"))
    )
    (net (code "36") (name "Net-(BLK3-B)") (class "Default")
      (node (ref "BLK3") (pin "8") (pinfunction "B_8") (pintype "passive"))
      (node (ref "U5") (pin "12") (pinfunction "B_12") (pintype "input"))
    )
    (net (code "37") (name "Net-(BLK3-C)") (class "Default")
      (node (ref "BLK3") (pin "7") (pinfunction "C_7") (pintype "passive"))
      (node (ref "U5") (pin "13") (pinfunction "C_13") (pintype "input"))
    )
    (net (code "38") (name "Net-(BLK3-D)") (class "Default")
      (node (ref "BLK3") (pin "6") (pinfunction "D_6") (pintype "passive"))
      (node (ref "U5") (pin "14") (pinfunction "D_14") (pintype "input"))
    )
    (net (code "39") (name "Net-(BLK3-E)") (class "Default")
      (node (ref "BLK3") (pin "1") (pinfunction "E_1") (pintype "passive"))
      (node (ref "U5") (pin "3") (pinfunction "E_3") (pintype "input"))
    )
    (net (code "40") (name "Net-(BLK3-F)") (class "Default")
      (node (ref "BLK3") (pin "2") (pinfunction "F_2") (pintype "passive"))
      (node (ref "U5") (pin "4") (pinfunction "F_4") (pintype "input"))
    )
    (net (code "41") (name "Net-(BLK3-G)") (class "Default")
      (node (ref "BLK3") (pin "3") (pinfunction "G_3") (pintype "passive"))
      (node (ref "U5") (pin "5") (pinfunction "G_5") (pintype "input"))
    )
    (net (code "42") (name "Net-(BLK3-H)") (class "Default")
      (node (ref "BLK3") (pin "4") (pinfunction "H_4") (pintype "passive"))
      (node (ref "R22") (pin "1") (pinfunction "1_1") (pintype "passive"))
      (node (ref "U5") (pin "6") (pinfunction "H_6") (pintype "input"))
    )
    (net (code "43") (name "Net-(D1-C)") (class "Default")
      (node (ref "D1") (pin "1") (pinfunction "C_1") (pintype "passive"))
      (node (ref "R15") (pin "1") (pinfunction "1_1") (pintype "passive"))
    )
    (net (code "44") (name "Net-(D2-C)") (class "Default")
      (node (ref "D2") (pin "1") (pinfunction "C_1") (pintype "passive"))
      (node (ref "R16") (pin "1") (pinfunction "1_1") (pintype "passive"))
    )
    (net (code "45") (name "Net-(D3A-1_CATHODE)") (class "Default")
      (node (ref "D3") (pin "20") (pinfunction "1_CATHODE_20") (pintype "passive"))
      (node (ref "U8") (pin "10") (pinfunction "LED_NO.10_10") (pintype "passive"))
    )
    (net (code "46") (name "Net-(D3B-2_CATHODE)") (class "Default")
      (node (ref "D3") (pin "19") (pinfunction "2_CATHODE_19") (pintype "passive"))
      (node (ref "U8") (pin "11") (pinfunction "LED_NO.9_11") (pintype "passive"))
    )
    (net (code "47") (name "Net-(D3C-3_CATHODE)") (class "Default")
      (node (ref "D3") (pin "18") (pinfunction "3_CATHODE_18") (pintype "passive"))
      (node (ref "U8") (pin "12") (pinfunction "LED_NO.8_12") (pintype "passive"))
    )
    (net (code "48") (name "Net-(D3D-4_CATHODE)") (class "Default")
      (node (ref "D3") (pin "17") (pinfunction "4_CATHODE_17") (pintype "passive"))
      (node (ref "U8") (pin "13") (pinfunction "LED_NO.7_13") (pintype "passive"))
    )
    (net (code "49") (name "Net-(D3E-5_CATHODE)") (class "Default")
      (node (ref "D3") (pin "16") (pinfunction "5_CATHODE_16") (pintype "passive"))
      (node (ref "U8") (pin "14") (pinfunction "LED_NO.6_14") (pintype "passive"))
    )
    (net (code "50") (name "Net-(D3F-6_CATHODE)") (class "Default")
      (node (ref "D3") (pin "15") (pinfunction "6_CATHODE_15") (pintype "passive"))
      (node (ref "U8") (pin "15") (pinfunction "LED_NO.5_15") (pintype "passive"))
    )
    (net (code "51") (name "Net-(D3G-7_CATHODE)") (class "Default")
      (node (ref "D3") (pin "14") (pinfunction "7_CATHODE_14") (pintype "passive"))
      (node (ref "U8") (pin "16") (pinfunction "LED_NO.4_16") (pintype "passive"))
    )
    (net (code "52") (name "Net-(D3H-8_CATHODE)") (class "Default")
      (node (ref "D3") (pin "13") (pinfunction "8_CATHODE_13") (pintype "passive"))
      (node (ref "U8") (pin "17") (pinfunction "LED_NO.3_17") (pintype "passive"))
    )
    (net (code "53") (name "Net-(D3I-9_CATHODE)") (class "Default")
      (node (ref "D3") (pin "12") (pinfunction "9_CATHODE_12") (pintype "passive"))
      (node (ref "U8") (pin "18") (pinfunction "LED_NO.2_18") (pintype "passive"))
    )
    (net (code "54") (name "Net-(D3J-10_CATHODE)") (class "Default")
      (node (ref "D3") (pin "11") (pinfunction "10_CATHODE_11") (pintype "passive"))
      (node (ref "U8") (pin "1") (pinfunction "LED_NO.1_1") (pintype "passive"))
    )
    (net (code "55") (name "Net-(J1-Vin)") (class "Default")
      (node (ref "C1") (pin "1") (pinfunction "1_1") (pintype "passive"))
      (node (ref "J1") (pin "1") (pinfunction "Vin_1") (pintype "passive"))
      (node (ref "U9") (pin "1") (pinfunction "IN_1") (pintype "input"))
    )
    (net (code "56") (name "Net-(SD1-a)") (class "Default")
      (node (ref "R3") (pin "2") (pinfunction "2_2") (pintype "passive"))
      (node (ref "SD1") (pin "2") (pinfunction "a_2") (pintype "passive"))
    )
    (net (code "57") (name "Net-(SD1-b)") (class "Default")
      (node (ref "R1") (pin "2") (pinfunction "2_2") (pintype "passive"))
      (node (ref "SD1") (pin "1") (pinfunction "b_1") (pintype "passive"))
    )
    (net (code "58") (name "Net-(SD1-c)") (class "Default")
      (node (ref "R11") (pin "2") (pinfunction "2_2") (pintype "passive"))
      (node (ref "SD1") (pin "9") (pinfunction "c_9") (pintype "passive"))
    )
    (net (code "59") (name "Net-(SD1-d)") (class "Default")
      (node (ref "R13") (pin "2") (pinfunction "2_2") (pintype "passive"))
      (node (ref "SD1") (pin "7") (pinfunction "d_7") (pintype "passive"))
    )
    (net (code "60") (name "Net-(SD1-e)") (class "Default")
      (node (ref "R9") (pin "2") (pinfunction "2_2") (pintype "passive"))
      (node (ref "SD1") (pin "6") (pinfunction "e_6") (pintype "passive"))
    )
    (net (code "61") (name "Net-(SD1-f)") (class "Default")
      (node (ref "R5") (pin "2") (pinfunction "2_2") (pintype "passive"))
      (node (ref "SD1") (pin "4") (pinfunction "f_4") (pintype "passive"))
    )
    (net (code "62") (name "Net-(SD1-g)") (class "Default")
      (node (ref "R7") (pin "2") (pinfunction "2_2") (pintype "passive"))
      (node (ref "SD1") (pin "5") (pinfunction "g_5") (pintype "passive"))
    )
    (net (code "63") (name "Net-(SD2-a)") (class "Default")
      (node (ref "R6") (pin "1") (pinfunction "1_1") (pintype "passive"))
      (node (ref "SD2") (pin "2") (pinfunction "a_2") (pintype "passive"))
    )
    (net (code "64") (name "Net-(SD2-b)") (class "Default")
      (node (ref "R8") (pin "1") (pinfunction "1_1") (pintype "passive"))
      (node (ref "SD2") (pin "1") (pinfunction "b_1") (pintype "passive"))
    )
    (net (code "65") (name "Net-(SD2-c)") (class "Default")
      (node (ref "R10") (pin "1") (pinfunction "1_1") (pintype "passive"))
      (node (ref "SD2") (pin "9") (pinfunction "c_9") (pintype "passive"))
    )
    (net (code "66") (name "Net-(SD2-d)") (class "Default")
      (node (ref "R14") (pin "1") (pinfunction "1_1") (pintype "passive"))
      (node (ref "SD2") (pin "7") (pinfunction "d_7") (pintype "passive"))
    )
    (net (code "67") (name "Net-(SD2-e)") (class "Default")
      (node (ref "R12") (pin "1") (pinfunction "1_1") (pintype "passive"))
      (node (ref "SD2") (pin "6") (pinfunction "e_6") (pintype "passive"))
    )
    (net (code "68") (name "Net-(SD2-f)") (class "Default")
      (node (ref "R4") (pin "1") (pinfunction "1_1") (pintype "passive"))
      (node (ref "SD2") (pin "4") (pinfunction "f_4") (pintype "passive"))
    )
    (net (code "69") (name "Net-(SD2-g)") (class "Default")
      (node (ref "R2") (pin "1") (pinfunction "1_1") (pintype "passive"))
      (node (ref "SD2") (pin "5") (pinfunction "g_5") (pintype "passive"))
    )
    (net (code "70") (name "Net-(U1-A)") (class "Default")
      (node (ref "RP4") (pin "6") (pinfunction "6_6") (pintype "passive"))
      (node (ref "U1") (pin "7") (pinfunction "A_7") (pintype "input"))
      (node (ref "U6") (pin "4") (pinfunction "QE_4") (pintype "tri_state"))
    )
    (net (code "71") (name "Net-(U1-B)") (class "Default")
      (node (ref "RP4") (pin "7") (pinfunction "7_7") (pintype "passive"))
      (node (ref "U1") (pin "1") (pinfunction "B_1") (pintype "input"))
      (node (ref "U6") (pin "5") (pinfunction "QF_5") (pintype "tri_state"))
    )
    (net (code "72") (name "Net-(U1-C)") (class "Default")
      (node (ref "RP4") (pin "8") (pinfunction "8_8") (pintype "passive"))
      (node (ref "U1") (pin "2") (pinfunction "C_2") (pintype "input"))
      (node (ref "U6") (pin "6") (pinfunction "QG_6") (pintype "tri_state"))
    )
    (net (code "73") (name "Net-(U1-D)") (class "Default")
      (node (ref "RP4") (pin "9") (pinfunction "9_9") (pintype "passive"))
      (node (ref "U1") (pin "6") (pinfunction "D_6") (pintype "input"))
      (node (ref "U6") (pin "7") (pinfunction "QH_7") (pintype "tri_state"))
    )
    (net (code "74") (name "Net-(U1-~{a})") (class "Default")
      (node (ref "R3") (pin "1") (pinfunction "1_1") (pintype "passive"))
      (node (ref "U1") (pin "13") (pinfunction "~{a}_13") (pintype "open_collector"))
    )
    (net (code "75") (name "Net-(U1-~{b})") (class "Default")
      (node (ref "R1") (pin "1") (pinfunction "1_1") (pintype "passive"))
      (node (ref "U1") (pin "12") (pinfunction "~{b}_12") (pintype "open_collector"))
    )
    (net (code "76") (name "Net-(U1-~{c})") (class "Default")
      (node (ref "R11") (pin "1") (pinfunction "1_1") (pintype "passive"))
      (node (ref "U1") (pin "11") (pinfunction "~{c}_11") (pintype "open_collector"))
    )
    (net (code "77") (name "Net-(U1-~{d})") (class "Default")
      (node (ref "R13") (pin "1") (pinfunction "1_1") (pintype "passive"))
      (node (ref "U1") (pin "10") (pinfunction "~{d}_10") (pintype "open_collector"))
    )
    (net (code "78") (name "Net-(U1-~{e})") (class "Default")
      (node (ref "R9") (pin "1") (pinfunction "1_1") (pintype "passive"))
      (node (ref "U1") (pin "9") (pinfunction "~{e}_9") (pintype "open_collector"))
    )
    (net (code "79") (name "Net-(U1-~{f})") (class "Default")
      (node (ref "R5") (pin "1") (pinfunction "1_1") (pintype "passive"))
      (node (ref "U1") (pin "15") (pinfunction "~{f}_15") (pintype "open_collector"))
    )
    (net (code "80") (name "Net-(U1-~{g})") (class "Default")
      (node (ref "R7") (pin "1") (pinfunction "1_1") (pintype "passive"))
      (node (ref "U1") (pin "14") (pinfunction "~{g}_14") (pintype "open_collector"))
    )
    (net (code "81") (name "Net-(U2-A)") (class "Default")
      (node (ref "RP4") (pin "2") (pinfunction "2_2") (pintype "passive"))
      (node (ref "U2") (pin "7") (pinfunction "A_7") (pintype "input"))
      (node (ref "U6") (pin "15") (pinfunction "QA_15") (pintype "tri_state"))
    )
    (net (code "82") (name "Net-(U2-B)") (class "Default")
      (node (ref "RP4") (pin "3") (pinfunction "3_3") (pintype "passive"))
      (node (ref "U2") (pin "1") (pinfunction "B_1") (pintype "input"))
      (node (ref "U6") (pin "1") (pinfunction "QB_1") (pintype "tri_state"))
    )
    (net (code "83") (name "Net-(U2-C)") (class "Default")
      (node (ref "RP4") (pin "4") (pinfunction "4_4") (pintype "passive"))
      (node (ref "U2") (pin "2") (pinfunction "C_2") (pintype "input"))
      (node (ref "U6") (pin "2") (pinfunction "QC_2") (pintype "tri_state"))
    )
    (net (code "84") (name "Net-(U2-D)") (class "Default")
      (node (ref "RP4") (pin "5") (pinfunction "5_5") (pintype "passive"))
      (node (ref "U2") (pin "6") (pinfunction "D_6") (pintype "input"))
      (node (ref "U6") (pin "3") (pinfunction "QD_3") (pintype "tri_state"))
    )
    (net (code "85") (name "Net-(U2-~{a})") (class "Default")
      (node (ref "R6") (pin "2") (pinfunction "2_2") (pintype "passive"))
      (node (ref "U2") (pin "13") (pinfunction "~{a}_13") (pintype "open_collector"))
    )
    (net (code "86") (name "Net-(U2-~{b})") (class "Default")
      (node (ref "R8") (pin "2") (pinfunction "2_2") (pintype "passive"))
      (node (ref "U2") (pin "12") (pinfunction "~{b}_12") (pintype "open_collector"))
    )
    (net (code "87") (name "Net-(U2-~{c})") (class "Default")
      (node (ref "R10") (pin "2") (pinfunction "2_2") (pintype "passive"))
      (node (ref "U2") (pin "11") (pinfunction "~{c}_11") (pintype "open_collector"))
    )
    (net (code "88") (name "Net-(U2-~{d})") (class "Default")
      (node (ref "R14") (pin "2") (pinfunction "2_2") (pintype "passive"))
      (node (ref "U2") (pin "10") (pinfunction "~{d}_10") (pintype "open_collector"))
    )
    (net (code "89") (name "Net-(U2-~{e})") (class "Default")
      (node (ref "R12") (pin "2") (pinfunction "2_2") (pintype "passive"))
      (node (ref "U2") (pin "9") (pinfunction "~{e}_9") (pintype "open_collector"))
    )
    (net (code "90") (name "Net-(U2-~{f})") (class "Default")
      (node (ref "R4") (pin "2") (pinfunction "2_2") (pintype "passive"))
      (node (ref "U2") (pin "15") (pinfunction "~{f}_15") (pintype "open_collector"))
    )
    (net (code "91") (name "Net-(U2-~{g})") (class "Default")
      (node (ref "R2") (pin "2") (pinfunction "2_2") (pintype "passive"))
      (node (ref "U2") (pin "14") (pinfunction "~{g}_14") (pintype "open_collector"))
    )
    (net (code "92") (name "Net-(U7-PB6_(PCINT6{slash}XTAL1{slash}TOSC1))") (class "Default")
      (node (ref "C4") (pin "2") (pinfunction "2_2") (pintype "passive"))
      (node (ref "U7") (pin "9") (pinfunction "PB6_(PCINT6/XTAL1/TOSC1)_9") (pintype "bidirectional"))
      (node (ref "X1") (pin "1") (pinfunction "1_1") (pintype "passive"))
    )
    (net (code "93") (name "Net-(U7-PB7_(PCINT7{slash}XTAL2{slash}TOSC2))") (class "Default")
      (node (ref "C3") (pin "2") (pinfunction "2_2") (pintype "passive"))
      (node (ref "U7") (pin "10") (pinfunction "PB7_(PCINT7/XTAL2/TOSC2)_10") (pintype "bidirectional"))
      (node (ref "X1") (pin "2") (pinfunction "2_2") (pintype "passive"))
    )
    (net (code "94") (name "Net-(U8-DIVIDER(HIGH_END))") (class "Default")
      (node (ref "R18") (pin "2") (pinfunction "2_2") (pintype "passive"))
      (node (ref "U8") (pin "6") (pinfunction "DIVIDER(HIGH_END)_6") (pintype "passive"))
      (node (ref "U8") (pin "7") (pinfunction "REFERENCE_OUTPUT_7") (pintype "passive"))
    )
    (net (code "95") (name "Net-(U8-REFERENCE_ADJUST)") (class "Default")
      (node (ref "R17") (pin "1") (pinfunction "1_1") (pintype "passive"))
      (node (ref "R18") (pin "1") (pinfunction "1_1") (pintype "passive"))
      (node (ref "U8") (pin "8") (pinfunction "REFERENCE_ADJUST_8") (pintype "passive"))
    )
    (net (code "96") (name "Net-(U8-SIGNAL_INPUT)") (class "Default")
      (node (ref "C5") (pin "2") (pinfunction "2_2") (pintype "passive"))
      (node (ref "R19") (pin "2") (pinfunction "2_2") (pintype "passive"))
      (node (ref "U8") (pin "5") (pinfunction "SIGNAL_INPUT_5") (pintype "passive"))
    )
    (net (code "97") (name "VCC") (class "Default")
      (node (ref "BLK1") (pin "5") (pinfunction "VCC_5") (pintype "passive"))
      (node (ref "BLK2") (pin "5") (pinfunction "VCC_5") (pintype "passive"))
      (node (ref "BLK3") (pin "5") (pinfunction "VCC_5") (pintype "passive"))
      (node (ref "C2") (pin "1") (pinfunction "1_1") (pintype "passive"))
      (node (ref "D3") (pin "1") (pinfunction "1_ANODE_1") (pintype "passive"))
      (node (ref "D3") (pin "10") (pinfunction "10_ANODE_10") (pintype "passive"))
      (node (ref "D3") (pin "2") (pinfunction "2_ANODE_2") (pintype "passive"))
      (node (ref "D3") (pin "3") (pinfunction "3_ANODE_3") (pintype "passive"))
      (node (ref "D3") (pin "4") (pinfunction "4_ANODE_4") (pintype "passive"))
      (node (ref "D3") (pin "5") (pinfunction "5_ANODE_5") (pintype "passive"))
      (node (ref "D3") (pin "6") (pinfunction "6_ANODE_6") (pintype "passive"))
      (node (ref "D3") (pin "7") (pinfunction "7_ANODE_7") (pintype "passive"))
      (node (ref "D3") (pin "8") (pinfunction "8_ANODE_8") (pintype "passive"))
      (node (ref "D3") (pin "9") (pinfunction "9_ANODE_9") (pintype "passive"))
      (node (ref "SD1") (pin "3") (pinfunction "vcc_3") (pintype "passive"))
      (node (ref "SD1") (pin "8") (pinfunction "vcc_8") (pintype "passive"))
      (node (ref "SD2") (pin "3") (pinfunction "vcc_3") (pintype "passive"))
      (node (ref "SD2") (pin "8") (pinfunction "vcc_8") (pintype "passive"))
      (node (ref "U1") (pin "16") (pinfunction "VCC_16") (pintype "power_in"))
      (node (ref "U1") (pin "3") (pinfunction "~{LT}_3") (pintype "input"))
      (node (ref "U1") (pin "5") (pinfunction "~{RBI}_5") (pintype "input"))
      (node (ref "U2") (pin "16") (pinfunction "VCC_16") (pintype "power_in"))
      (node (ref "U2") (pin "3") (pinfunction "~{LT}_3") (pintype "input"))
      (node (ref "U2") (pin "5") (pinfunction "~{RBI}_5") (pintype "input"))
      (node (ref "U3") (pin "16") (pinfunction "VCC_16") (pintype "power_in"))
      (node (ref "U4") (pin "16") (pinfunction "VCC_16") (pintype "power_in"))
      (node (ref "U5") (pin "16") (pinfunction "VCC_16") (pintype "power_in"))
      (node (ref "U6") (pin "10") (pinfunction "~{SRCLR}_10") (pintype "input"))
      (node (ref "U6") (pin "16") (pinfunction "VCC_16") (pintype "power_in"))
      (node (ref "U7") (pin "20") (pinfunction "AVCC_20") (pintype "power_in"))
      (node (ref "U7") (pin "21") (pinfunction "AREF_21") (pintype "power_in"))
      (node (ref "U7") (pin "7") (pinfunction "VCC_7") (pintype "power_in"))
      (node (ref "U8") (pin "3") (pinfunction "V+_3") (pintype "power_in"))
      (node (ref "U8") (pin "9") (pinfunction "MODE_SELECT_9") (pintype "input"))
      (node (ref "U9") (pin "3") (pinfunction "OUT_3") (pintype "passive"))
    )
    (net (code "98") (name "unconnected-(PTH1-Pad1)") (class "Default")
      (node (ref "PTH1") (pin "1") (pinfunction "1_1") (pintype "passive"))
    )
    (net (code "99") (name "unconnected-(PTH2-Pad1)") (class "Default")
      (node (ref "PTH2") (pin "1") (pinfunction "1_1") (pintype "passive"))
    )
    (net (code "100") (name "unconnected-(PTH3-Pad1)") (class "Default")
      (node (ref "PTH3") (pin "1") (pinfunction "1_1") (pintype "passive"))
    )
    (net (code "101") (name "unconnected-(PTH4-Pad1)") (class "Default")
      (node (ref "PTH4") (pin "1") (pinfunction "1_1") (pintype "passive"))
    )
    (net (code "102") (name "unconnected-(SD1-dp-Pad10)") (class "Default")
      (node (ref "SD1") (pin "10") (pinfunction "dp_10") (pintype "passive"))
    )
    (net (code "103") (name "unconnected-(SD2-dp-Pad10)") (class "Default")
      (node (ref "SD2") (pin "10") (pinfunction "dp_10") (pintype "passive"))
    )
    (net (code "104") (name "unconnected-(SW1-Pad2)") (class "Default")
      (node (ref "SW1") (pin "2") (pinfunction "2_2") (pintype "passive"))
    )
    (net (code "105") (name "unconnected-(SW1-Pad4)") (class "Default")
      (node (ref "SW1") (pin "4") (pinfunction "4_4") (pintype "passive"))
    )
    (net (code "106") (name "unconnected-(SW2-Pad2)") (class "Default")
      (node (ref "SW2") (pin "2") (pinfunction "2_2") (pintype "passive"))
    )
    (net (code "107") (name "unconnected-(SW2-Pad4)") (class "Default")
      (node (ref "SW2") (pin "4") (pinfunction "4_4") (pintype "passive"))
    )
    (net (code "108") (name "unconnected-(U3-QH-Pad9)") (class "Default")
      (node (ref "U3") (pin "9") (pinfunction "QH_9") (pintype "output"))
    )
    (net (code "109") (name "unconnected-(U4-QH-Pad9)") (class "Default")
      (node (ref "U4") (pin "9") (pinfunction "QH_9") (pintype "output"))
    )
    (net (code "110") (name "unconnected-(U5-QH-Pad9)") (class "Default")
      (node (ref "U5") (pin "9") (pinfunction "QH_9") (pintype "output"))
    )
    (net (code "111") (name "unconnected-(U6-QH'-Pad9)") (class "Default")
      (node (ref "U6") (pin "9") (pinfunction "QH'_9") (pintype "output"))
    )
    (net (code "112") (name "unconnected-(U7-PB5_(SCK{slash}PCINT5)-Pad19)") (class "Default")
      (node (ref "U7") (pin "19") (pinfunction "PB5_(SCK/PCINT5)_19") (pintype "bidirectional"))
    )
    (net (code "113") (name "unconnected-(U7-PC0_(ADC0{slash}PCINT8)-Pad23)") (class "Default")
      (node (ref "U7") (pin "23") (pinfunction "PC0_(ADC0/PCINT8)_23") (pintype "bidirectional"))
    )
    (net (code "114") (name "unconnected-(U7-PC4_(ADC4{slash}SDA{slash}PCINT12)-Pad27)") (class "Default")
      (node (ref "U7") (pin "27") (pinfunction "PC4_(ADC4/SDA/PCINT12)_27") (pintype "bidirectional"))
    )
    (net (code "115") (name "unconnected-(U7-PC5_(ADC5{slash}SCL{slash}PCINT13)-Pad28)") (class "Default")
      (node (ref "U7") (pin "28") (pinfunction "PC5_(ADC5/SCL/PCINT13)_28") (pintype "bidirectional"))
    )
    (net (code "116") (name "unconnected-(U7-PC6_(PCINT14{slash}~{RESET})-Pad1)") (class "Default")
      (node (ref "U7") (pin "1") (pinfunction "PC6_(PCINT14/~{RESET})_1") (pintype "bidirectional"))
    )
    (net (code "117") (name "unconnected-(U7-PD0_(PCINT16{slash}RXD)-Pad2)") (class "Default")
      (node (ref "U7") (pin "2") (pinfunction "PD0_(PCINT16/RXD)_2") (pintype "bidirectional"))
    )
    (net (code "118") (name "unconnected-(U7-PD1_(PCINT17{slash}TXD)-Pad3)") (class "Default")
      (node (ref "U7") (pin "3") (pinfunction "PD1_(PCINT17/TXD)_3") (pintype "bidirectional"))
    )
    (net (code "119") (name "unconnected-(U7-PD6_(PCINT22{slash}OC0A{slash}AIN0)-Pad12)") (class "Default")
      (node (ref "U7") (pin "12") (pinfunction "PD6_(PCINT22/OC0A/AIN0)_12") (pintype "bidirectional"))
    )
  )
)
